# VoltageRegulator.net
KiCad netlist of a schematic drawn in Altium Designer
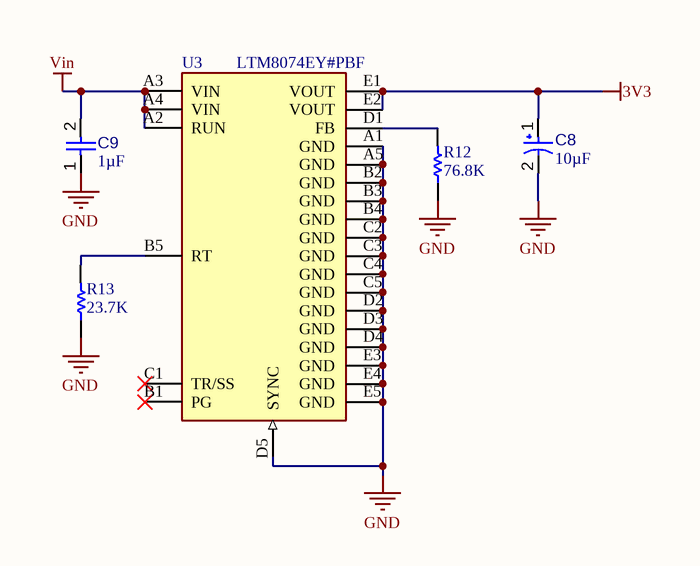
[diagram p0: VoltageRegulator.SchDoc]

(export (version "E")
  (design (tool "Eeschema 10.0.6"))
  (components
    (comp (ref "C8")
      (value "10µF")
      (footprint "CAPMP3217X18-T_V")
      (description "Standard Tantalum, 10 uF, +/- 10%, 16 V, -55 to 125 degC, 1206 (3216 Metric), RoHS, Tape and Reel")
      (fields (field (name "TOLERANCE") "10%") (field (name "MANUFACTURER") "AVX"))
      (libsource (lib "Bronco Racing") (part "CAP-P-2"))
    )
    (comp (ref "C9")
      (value "1µF")
      (footprint "CAPC0603(1608)100_L")
      (description "Chip Capacitor, 1µF +/-40%, 50V, 0603, Thickness 1 mm")
      (fields (field (name "TOLERANCE") "10%") (field (name "Comment") "Capacitor 1µF +/-40% 50V 0603"))
      (libsource (lib "Bronco Racing") (part "CAP-NP-2"))
    )
    (comp (ref "R12")
      (value "76.8K")
      (footprint "RESC1609X50X30ML10T20")
      (fields (field (name "PART NUMBER") "CRCW060376K8FKEA") (field (name "MANUFACTURER") "Vishay Dale"))
      (libsource (lib "Altium Content Vault") (part "RES"))
    )
    (comp (ref "R13")
      (value "23.7K")
      (footprint "RESC1608X55X30ML15T15")
      (fields (field (name "PART NUMBER") "ERJ-3EKF2372V") (field (name "MANUFACTURER") "Panasonic"))
      (libsource (lib "Altium Content Vault") (part "RES"))
    )
    (comp (ref "U3")
      (value "LTM8074EY#PBF")
      (footprint "FP-BGA-25-05-08-1566-MFG")
      (description "IC REG BUCK ADJ 1.2A 25BGA")
      (fields
        (field (name "MANUFACTURER") "Analog Devices")
        (field (name "OCTOPART") "https://octopart.com/ltm8074ey%23pbf-analog+devices-95880170")
      )
      (libsource (lib "Altium Content Vault") (part "9e9da4b837be4f4c72679088a9770a1"))
    )
  )
  (nets
    (net (code "1") (name "3V3") (class "Default")
      (node (ref "C8") (pin "1") (pinfunction "1_1") (pintype "passive"))
      (node (ref "U3") (pin "E1") (pinfunction "VOUT_E1") (pintype "power_in"))
      (node (ref "U3") (pin "E2") (pinfunction "VOUT_E2") (pintype "power_in"))
    )
    (net (code "2") (name "GND") (class "Default")
      (node (ref "C8") (pin "2") (pinfunction "2_2") (pintype "passive"))
      (node (ref "C9") (pin "1") (pinfunction "1_1") (pintype "passive"))
      (node (ref "R12") (pin "1") (pinfunction "1_1") (pintype "passive"))
      (node (ref "R13") (pin "1") (pinfunction "1_1") (pintype "passive"))
      (node (ref "U3") (pin "A1") (pinfunction "GND_A1") (pintype "power_in"))
      (node (ref "U3") (pin "A5") (pinfunction "GND_A5") (pintype "power_in"))
      (node (ref "U3") (pin "B2") (pinfunction "GND_B2") (pintype "power_in"))
      (node (ref "U3") (pin "B3") (pinfunction "GND_B3") (pintype "power_in"))
      (node (ref "U3") (pin "B4") (pinfunction "GND_B4") (pintype "power_in"))
      (node (ref "U3") (pin "C2") (pinfunction "GND_C2") (pintype "power_in"))
      (node (ref "U3") (pin "C3") (pinfunction "GND_C3") (pintype "power_in"))
      (node (ref "U3") (pin "C4") (pinfunction "GND_C4") (pintype "power_in"))
      (node (ref "U3") (pin "C5") (pinfunction "GND_C5") (pintype "power_in"))
      (node (ref "U3") (pin "D2") (pinfunction "GND_D2") (pintype "power_in"))
      (node (ref "U3") (pin "D3") (pinfunction "GND_D3") (pintype "power_in"))
      (node (ref "U3") (pin "D4") (pinfunction "GND_D4") (pintype "power_in"))
      (node (ref "U3") (pin "D5") (pinfunction "SYNC_D5") (pintype "input"))
      (node (ref "U3") (pin "E3") (pinfunction "GND_E3") (pintype "power_in"))
      (node (ref "U3") (pin "E4") (pinfunction "GND_E4") (pintype "power_in"))
      (node (ref "U3") (pin "E5") (pinfunction "GND_E5") (pintype "power_in"))
    )
    (net (code "3") (name "Net-(U3-FB)") (class "Default")
      (node (ref "R12") (pin "2") (pinfunction "2_2") (pintype "passive"))
      (node (ref "U3") (pin "D1") (pinfunction "FB_D1") (pintype "passive"))
    )
    (net (code "4") (name "Net-(U3-RT)") (class "Default")
      (node (ref "R13") (pin "2") (pinfunction "2_2") (pintype "passive"))
      (node (ref "U3") (pin "B5") (pinfunction "RT_B5") (pintype "passive"))
    )
    (net (code "5") (name "Vin") (class "Default")
      (node (ref "C9") (pin "2") (pinfunction "2_2") (pintype "passive"))
      (node (ref "U3") (pin "A2") (pinfunction "RUN_A2") (pintype "passive"))
      (node (ref "U3") (pin "A3") (pinfunction "VIN_A3") (pintype "power_in"))
      (node (ref "U3") (pin "A4") (pinfunction "VIN_A4") (pintype "power_in"))
    )
    (net (code "6") (name "unconnected-(U3-PG-PadB1)") (class "Default")
      (node (ref "U3") (pin "B1") (pinfunction "PG_B1") (pintype "open_collector+no_connect"))
    )
    (net (code "7") (name "unconnected-(U3-TR{slash}SS-PadC1)") (class "Default")
      (node (ref "U3") (pin "C1") (pinfunction "TR/SS_C1") (pintype "passive+no_connect"))
    )
  )
)
